# BFFL.net
KiCad netlist of a schematic drawn in EAGLE
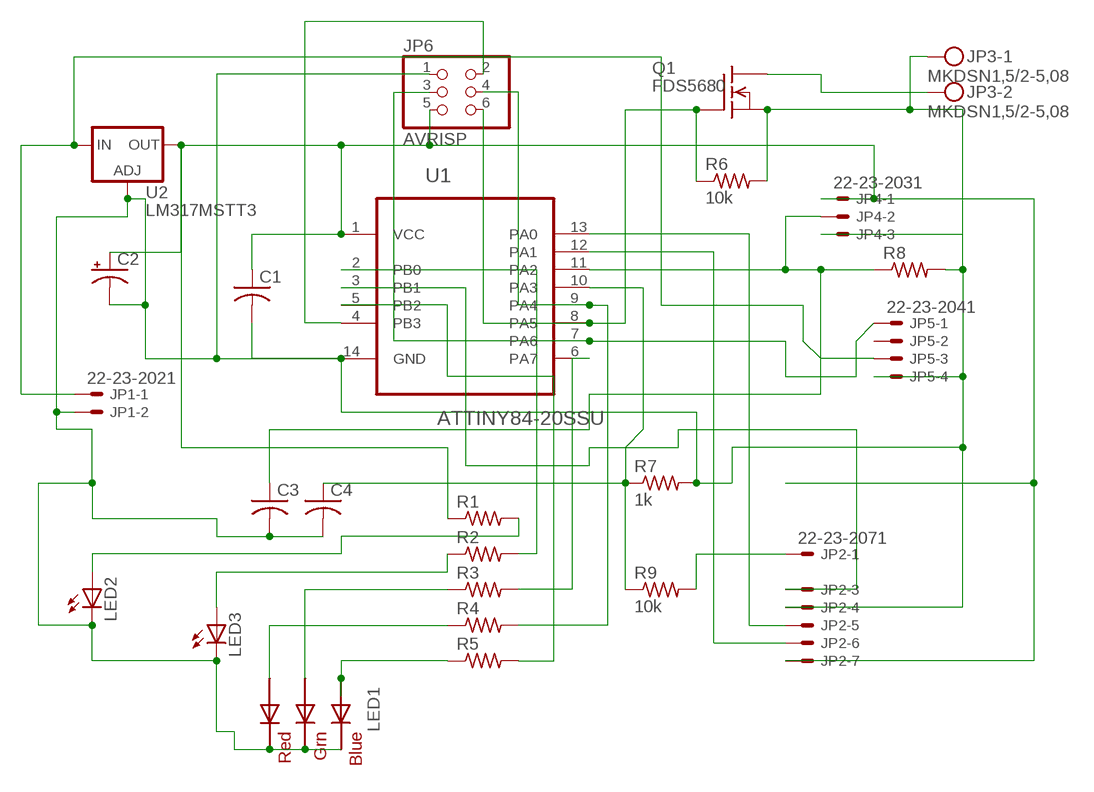
[diagram p0: schematic, sheet 1]

(export (version "E")
  (design (tool "Eeschema 10.0.6"))
  (components
    (comp (ref "C1")
      (value "C-USC1206K")
      (footprint "eagle-import:C1206K")
      (libsource (lib "eagle-import") (part "C-USC1206K"))
    )
    (comp (ref "C2")
      (value "CPOL-USC/6032-28W")
      (footprint "eagle-import:C_6032-28W")
      (libsource (lib "eagle-import") (part "CPOL-USC/6032-28W"))
    )
    (comp (ref "C3")
      (value "C-USC1206K")
      (footprint "eagle-import:C1206K")
      (libsource (lib "eagle-import") (part "C-USC1206K"))
    )
    (comp (ref "C4")
      (value "C-USC1206K")
      (footprint "eagle-import:C1206K")
      (libsource (lib "eagle-import") (part "C-USC1206K"))
    )
    (comp (ref "JP1")
      (value "22-23-2021")
      (footprint "eagle-import:22-23-2021")
      (fields (field (name "MF") "MOLEX"))
      (libsource (lib "eagle-import") (part "22-23-2021"))
    )
    (comp (ref "JP2")
      (value "22-23-2071")
      (footprint "eagle-import:22-23-2071")
      (fields (field (name "MF") "MOLEX"))
      (libsource (lib "eagle-import") (part "22-23-2071"))
    )
    (comp (ref "JP3")
      (value "MKDSN1,5/2-5,08")
      (footprint "eagle-import:MKDSN1,5_2-5,08")
      (fields (field (name "MPN") "MKDSN 1,5/2-5.08"))
      (libsource (lib "eagle-import") (part "MKDSN1,5/2-5,08"))
    )
    (comp (ref "JP4")
      (value "22-23-2031")
      (footprint "eagle-import:22-23-2031")
      (fields (field (name "MF") "MOLEX"))
      (libsource (lib "eagle-import") (part "22-23-2031"))
    )
    (comp (ref "JP5")
      (value "22-23-2041")
      (footprint "eagle-import:22-23-2041")
      (fields (field (name "MF") "MOLEX"))
      (libsource (lib "eagle-import") (part "22-23-2041"))
    )
    (comp (ref "JP6")
      (value "AVRISP")
      (footprint "eagle-import:2X03")
      (libsource (lib "eagle-import") (part "PINHD-2X3"))
    )
    (comp (ref "LED1")
      (value "RGBLED5050")
      (footprint "eagle-import:RGBLED5050")
      (libsource (lib "eagle-import") (part "RGBLED5050"))
    )
    (comp (ref "LED2")
      (value "LEDCHIPLED_1206")
      (footprint "eagle-import:CHIPLED_1206")
      (libsource (lib "eagle-import") (part "LEDCHIPLED_1206"))
    )
    (comp (ref "LED3")
      (value "LEDCHIPLED_1206")
      (footprint "eagle-import:CHIPLED_1206")
      (libsource (lib "eagle-import") (part "LEDCHIPLED_1206"))
    )
    (comp (ref "Q1")
      (value "FDS5680")
      (footprint "eagle-import:SO-8")
      (libsource (lib "eagle-import") (part "FDS5680"))
    )
    (comp (ref "R1")
      (value "R-US_R1206")
      (footprint "eagle-import:R1206")
      (libsource (lib "eagle-import") (part "R-US_R1206"))
    )
    (comp (ref "R2")
      (value "R-US_R1206")
      (footprint "eagle-import:R1206")
      (libsource (lib "eagle-import") (part "R-US_R1206"))
    )
    (comp (ref "R3")
      (value "R-US_R1206")
      (footprint "eagle-import:R1206")
      (libsource (lib "eagle-import") (part "R-US_R1206"))
    )
    (comp (ref "R4")
      (value "R-US_R1206")
      (footprint "eagle-import:R1206")
      (libsource (lib "eagle-import") (part "R-US_R1206"))
    )
    (comp (ref "R5")
      (value "R-US_R1206")
      (footprint "eagle-import:R1206")
      (libsource (lib "eagle-import") (part "R-US_R1206"))
    )
    (comp (ref "R6")
      (value "10k")
      (footprint "eagle-import:R1206")
      (libsource (lib "eagle-import") (part "R-US_R1206"))
    )
    (comp (ref "R7")
      (value "1k")
      (footprint "eagle-import:R1206")
      (libsource (lib "eagle-import") (part "R-US_R1206"))
    )
    (comp (ref "R8")
      (value "R-US_R1206")
      (footprint "eagle-import:R1206")
      (libsource (lib "eagle-import") (part "R-US_R1206"))
    )
    (comp (ref "R9")
      (value "10k")
      (footprint "eagle-import:R1206")
      (libsource (lib "eagle-import") (part "R-US_R1206"))
    )
    (comp (ref "U1")
      (value "ATTINY84-20SSU")
      (footprint "eagle-import:SOIC127P600X175-14N")
      (libsource (lib "eagle-import") (part "ATTINY84-20SSU"))
    )
    (comp (ref "U2")
      (value "LM317MSTT3")
      (footprint "eagle-import:SOT223")
      (libsource (lib "eagle-import") (part "LM317?MSTT3"))
    )
  )
  (nets
    (net (code "1") (name "Net-(JP1A-S)") (class "Default")
      (node (ref "JP1") (pin "1") (pinfunction "S_1") (pintype "passive"))
      (node (ref "JP5") (pin "3") (pinfunction "S_3") (pintype "passive"))
      (node (ref "U2") (pin "3") (pinfunction "IN_3") (pintype "input"))
    )
    (net (code "2") (name "Net-(JP1B-S)") (class "Default")
      (node (ref "C1") (pin "2") (pinfunction "2_2") (pintype "passive"))
      (node (ref "C2") (pin "-") (pinfunction "-_-") (pintype "passive"))
      (node (ref "C3") (pin "2") (pinfunction "2_2") (pintype "passive"))
      (node (ref "C4") (pin "2") (pinfunction "2_2") (pintype "passive"))
      (node (ref "JP1") (pin "2") (pinfunction "S_2") (pintype "passive"))
      (node (ref "JP2") (pin "4") (pinfunction "S_4") (pintype "passive"))
      (node (ref "JP3") (pin "1") (pinfunction "KL_1") (pintype "passive"))
      (node (ref "JP4") (pin "3") (pinfunction "S_3") (pintype "passive"))
      (node (ref "JP5") (pin "4") (pinfunction "S_4") (pintype "passive"))
      (node (ref "JP6") (pin "1") (pinfunction "1_1") (pintype "passive"))
      (node (ref "LED1") (pin "4") (pinfunction "BLUE_C_4") (pintype "bidirectional"))
      (node (ref "LED1") (pin "5") (pinfunction "RED_C_5") (pintype "bidirectional"))
      (node (ref "LED1") (pin "6") (pinfunction "GREEN_C_6") (pintype "bidirectional"))
      (node (ref "LED2") (pin "C") (pinfunction "C_C") (pintype "passive"))
      (node (ref "LED3") (pin "C") (pinfunction "C_C") (pintype "passive"))
      (node (ref "Q1") (pin "1") (pinfunction "S_1") (pintype "passive"))
      (node (ref "Q1") (pin "2") (pinfunction "S_2") (pintype "passive"))
      (node (ref "Q1") (pin "3") (pinfunction "S_3") (pintype "passive"))
      (node (ref "R6") (pin "2") (pinfunction "2_2") (pintype "passive"))
      (node (ref "R7") (pin "2") (pinfunction "2_2") (pintype "passive"))
      (node (ref "R8") (pin "2") (pinfunction "2_2") (pintype "passive"))
      (node (ref "U1") (pin "14") (pinfunction "GND_14") (pintype "passive"))
      (node (ref "U2") (pin "1") (pinfunction "ADJ_1") (pintype "input"))
    )
    (net (code "3") (name "Net-(JP2A-S)") (class "Default")
      (node (ref "JP2") (pin "1") (pinfunction "S_1") (pintype "passive"))
      (node (ref "R9") (pin "2") (pinfunction "2_2") (pintype "passive"))
    )
    (net (code "4") (name "Net-(JP2C-S)") (class "Default")
      (node (ref "JP2") (pin "3") (pinfunction "S_3") (pintype "passive"))
      (node (ref "U1") (pin "3") (pinfunction "PB1_3") (pintype "bidirectional"))
    )
    (net (code "5") (name "Net-(JP2E-S)") (class "Default")
      (node (ref "JP2") (pin "5") (pinfunction "S_5") (pintype "passive"))
      (node (ref "U1") (pin "13") (pinfunction "PA0_13") (pintype "bidirectional"))
    )
    (net (code "6") (name "Net-(JP2F-S)") (class "Default")
      (node (ref "JP2") (pin "6") (pinfunction "S_6") (pintype "passive"))
      (node (ref "U1") (pin "12") (pinfunction "PA1_12") (pintype "bidirectional"))
    )
    (net (code "7") (name "Net-(JP2G-S)") (class "Default")
      (node (ref "C1") (pin "1") (pinfunction "1_1") (pintype "passive"))
      (node (ref "C2") (pin "+") (pinfunction "+_+") (pintype "passive"))
      (node (ref "JP2") (pin "7") (pinfunction "S_7") (pintype "passive"))
      (node (ref "JP4") (pin "1") (pinfunction "S_1") (pintype "passive"))
      (node (ref "JP6") (pin "5") (pinfunction "5_5") (pintype "passive"))
      (node (ref "R1") (pin "1") (pinfunction "1_1") (pintype "passive"))
      (node (ref "U1") (pin "1") (pinfunction "VCC_1") (pintype "power_in"))
      (node (ref "U2") (pin "4") (pinfunction "OUT_4") (pintype "passive"))
    )
    (net (code "8") (name "Net-(JP3B-KL)") (class "Default")
      (node (ref "JP3") (pin "2") (pinfunction "KL_2") (pintype "passive"))
      (node (ref "Q1") (pin "5") (pinfunction "D_5") (pintype "passive"))
      (node (ref "Q1") (pin "6") (pinfunction "D_6") (pintype "passive"))
      (node (ref "Q1") (pin "7") (pinfunction "D_7") (pintype "passive"))
      (node (ref "Q1") (pin "8") (pinfunction "D_8") (pintype "passive"))
    )
    (net (code "9") (name "Net-(JP4B-S)") (class "Default")
      (node (ref "C3") (pin "1") (pinfunction "1_1") (pintype "passive"))
      (node (ref "JP4") (pin "2") (pinfunction "S_2") (pintype "passive"))
      (node (ref "R8") (pin "1") (pinfunction "1_1") (pintype "passive"))
      (node (ref "U1") (pin "11") (pinfunction "PA2_11") (pintype "bidirectional"))
    )
    (net (code "10") (name "Net-(JP5A-S)") (class "Default")
      (node (ref "JP5") (pin "1") (pinfunction "S_1") (pintype "passive"))
      (node (ref "JP6") (pin "3") (pinfunction "3_3") (pintype "passive"))
      (node (ref "U1") (pin "7") (pinfunction "PA6_7") (pintype "bidirectional"))
    )
    (net (code "11") (name "Net-(LED1-BLUE_A)") (class "Default")
      (node (ref "LED1") (pin "3") (pinfunction "BLUE_A_3") (pintype "bidirectional"))
      (node (ref "R5") (pin "1") (pinfunction "1_1") (pintype "passive"))
    )
    (net (code "12") (name "Net-(LED1-GREEN_A)") (class "Default")
      (node (ref "LED1") (pin "1") (pinfunction "GREEN_A_1") (pintype "bidirectional"))
      (node (ref "R3") (pin "1") (pinfunction "1_1") (pintype "passive"))
    )
    (net (code "13") (name "Net-(LED1-RED_A)") (class "Default")
      (node (ref "LED1") (pin "2") (pinfunction "RED_A_2") (pintype "bidirectional"))
      (node (ref "R4") (pin "1") (pinfunction "1_1") (pintype "passive"))
    )
    (net (code "14") (name "Net-(LED2-PadA)") (class "Default")
      (node (ref "LED2") (pin "A") (pinfunction "A_A") (pintype "passive"))
      (node (ref "R1") (pin "2") (pinfunction "2_2") (pintype "passive"))
    )
    (net (code "15") (name "Net-(LED3-PadA)") (class "Default")
      (node (ref "LED3") (pin "A") (pinfunction "A_A") (pintype "passive"))
      (node (ref "R2") (pin "1") (pinfunction "1_1") (pintype "passive"))
    )
    (net (code "16") (name "Net-(Q1-G)") (class "Default")
      (node (ref "JP6") (pin "6") (pinfunction "6_6") (pintype "passive"))
      (node (ref "Q1") (pin "4") (pinfunction "G_4") (pintype "passive"))
      (node (ref "R6") (pin "1") (pinfunction "1_1") (pintype "passive"))
      (node (ref "U1") (pin "8") (pinfunction "PA5_8") (pintype "bidirectional"))
    )
    (net (code "17") (name "Net-(U1-PA3)") (class "Default")
      (node (ref "C4") (pin "1") (pinfunction "1_1") (pintype "passive"))
      (node (ref "R7") (pin "1") (pinfunction "1_1") (pintype "passive"))
      (node (ref "R9") (pin "1") (pinfunction "1_1") (pintype "passive"))
      (node (ref "U1") (pin "10") (pinfunction "PA3_10") (pintype "bidirectional"))
    )
    (net (code "18") (name "Net-(U1-PA4)") (class "Default")
      (node (ref "JP6") (pin "4") (pinfunction "4_4") (pintype "passive"))
      (node (ref "R4") (pin "2") (pinfunction "2_2") (pintype "passive"))
      (node (ref "U1") (pin "9") (pinfunction "PA4_9") (pintype "bidirectional"))
    )
    (net (code "19") (name "Net-(U1-PA7)") (class "Default")
      (node (ref "R3") (pin "2") (pinfunction "2_2") (pintype "passive"))
      (node (ref "U1") (pin "6") (pinfunction "PA7_6") (pintype "bidirectional"))
    )
    (net (code "20") (name "Net-(U1-PB0)") (class "Default")
      (node (ref "R2") (pin "2") (pinfunction "2_2") (pintype "passive"))
      (node (ref "U1") (pin "2") (pinfunction "PB0_2") (pintype "bidirectional"))
    )
    (net (code "21") (name "Net-(U1-PB2)") (class "Default")
      (node (ref "R5") (pin "2") (pinfunction "2_2") (pintype "passive"))
      (node (ref "U1") (pin "5") (pinfunction "PB2_5") (pintype "bidirectional"))
    )
    (net (code "22") (name "Net-(U1-PB3)") (class "Default")
      (node (ref "JP6") (pin "2") (pinfunction "2_2") (pintype "passive"))
      (node (ref "U1") (pin "4") (pinfunction "PB3_4") (pintype "bidirectional"))
    )
    (net (code "23") (name "unconnected-(JP5B-S-Pad2)") (class "Default")
      (node (ref "JP5") (pin "2") (pinfunction "S_2") (pintype "passive"))
    )
  )
)
